# pfetreg.net
KiCad netlist of a schematic drawn in EAGLE
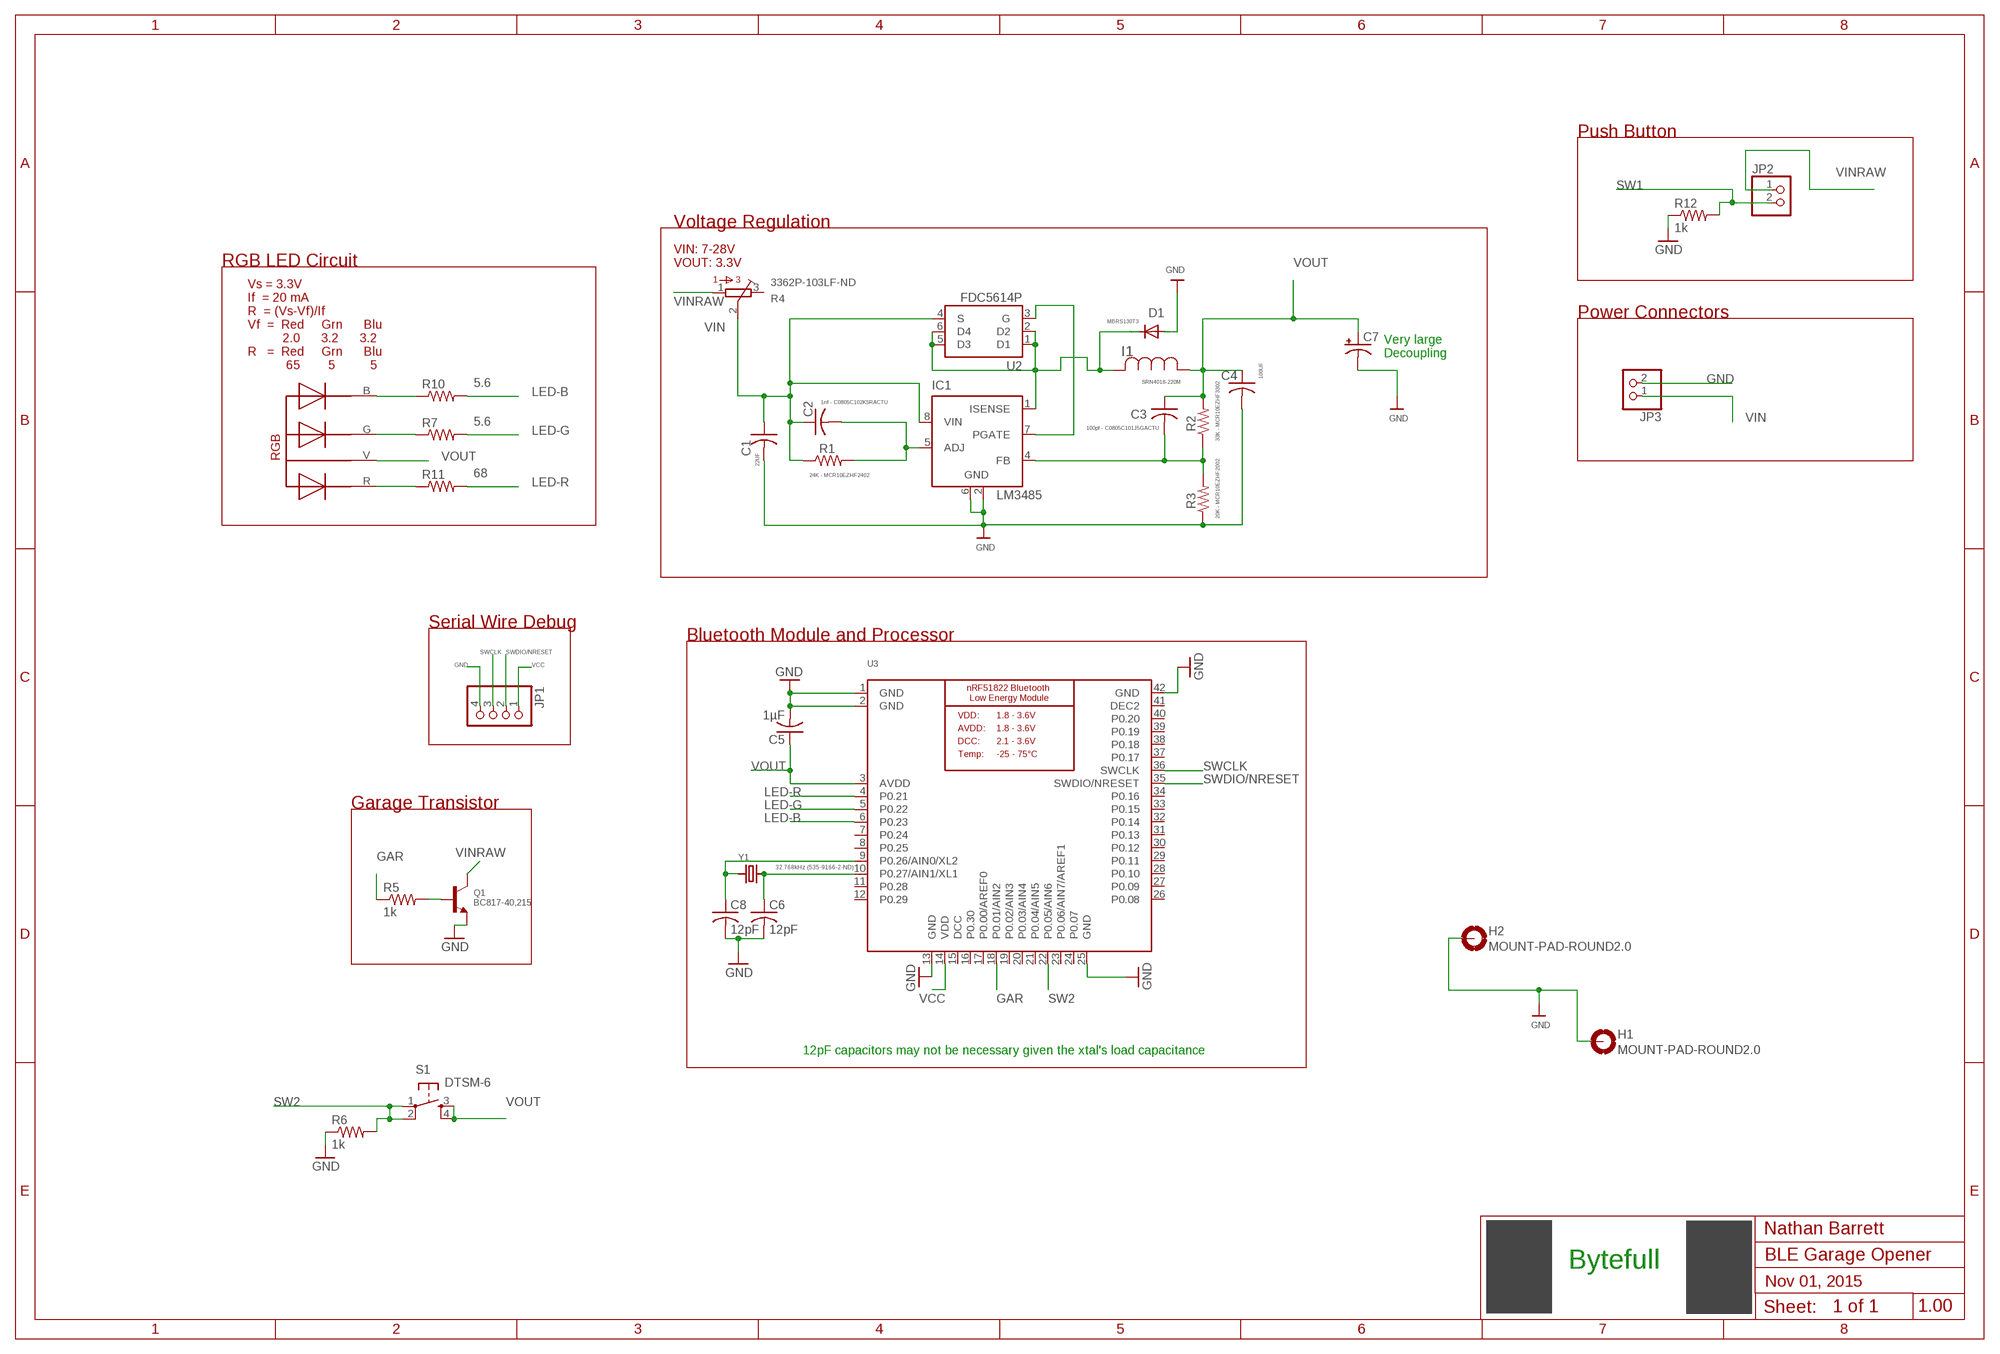
[diagram p0: schematic, sheet 1]

(export (version "E")
  (design (tool "Eeschema 10.0.6"))
  (components
    (comp (ref "C1")
      (value "22UF")
      (footprint "eagle-import:CAPCP7343X430N")
      (fields (field (name "MPN") "F931V226MNC"))
      (libsource (lib "eagle-import") (part "F931V226MNC"))
    )
    (comp (ref "C2")
      (value "1nf - C0805C102K5RACTU")
      (footprint "eagle-import:C0805K")
      (libsource (lib "eagle-import") (part "C-USC0805K"))
    )
    (comp (ref "C3")
      (value "100pf - C0805C101J5GACTU")
      (footprint "eagle-import:C0805K")
      (libsource (lib "eagle-import") (part "C-USC0805K"))
    )
    (comp (ref "C4")
      (value "100UF")
      (footprint "eagle-import:CAPCP7343X430N")
      (fields (field (name "MPN") "6TPC100M"))
      (libsource (lib "eagle-import") (part "6TPC100M"))
    )
    (comp (ref "C5")
      (value "1µF")
      (footprint "eagle-import:C0805K")
      (libsource (lib "eagle-import") (part "HelloWorld_C-USC0805K"))
    )
    (comp (ref "C6")
      (value "12pF")
      (footprint "eagle-import:C0805")
      (libsource (lib "eagle-import") (part "HelloWorld_C-USC0805"))
    )
    (comp (ref "C7")
      (value "CPOL-USE5-10.5")
      (footprint "eagle-import:E5-10,5")
      (libsource (lib "eagle-import") (part "CPOL-USE5-10.5"))
    )
    (comp (ref "C8")
      (value "12pF")
      (footprint "eagle-import:C0805")
      (libsource (lib "eagle-import") (part "HelloWorld_C-USC0805"))
    )
    (comp (ref "D1")
      (value "MBRS130T3")
      (footprint "eagle-import:DO214AA")
      (libsource (lib "eagle-import") (part "DIODE-DO214AA"))
    )
    (comp (ref "H1")
      (value "MOUNT-PAD-ROUND2.0")
      (footprint "eagle-import:2,0-PAD")
      (libsource (lib "eagle-import") (part "MOUNT-PAD-ROUND2.0"))
    )
    (comp (ref "H2")
      (value "MOUNT-PAD-ROUND2.0")
      (footprint "eagle-import:2,0-PAD")
      (libsource (lib "eagle-import") (part "MOUNT-PAD-ROUND2.0"))
    )
    (comp (ref "I1")
      (value "SRN4018-220M")
      (footprint "eagle-import:SRN4018-220M")
      (libsource (lib "eagle-import") (part "SRN4018-220M"))
    )
    (comp (ref "IC1")
      (value "LM3485")
      (footprint "eagle-import:MSOP08")
      (libsource (lib "eagle-import") (part "LM3485"))
    )
    (comp (ref "JP1")
      (value "PINHD-1X4")
      (footprint "eagle-import:1X04")
      (libsource (lib "eagle-import") (part "PINHD-1X4"))
    )
    (comp (ref "JP2")
      (value "PINHD-1X2")
      (footprint "eagle-import:1X02")
      (libsource (lib "eagle-import") (part "PINHD-1X2"))
    )
    (comp (ref "JP3")
      (value "PINHD-1X2")
      (footprint "eagle-import:1X02")
      (libsource (lib "eagle-import") (part "PINHD-1X2"))
    )
    (comp (ref "Q1")
      (value "BC817-40,215")
      (footprint "eagle-import:SOT23-R")
      (libsource (lib "eagle-import") (part "TRANSISTOR_NPN"))
    )
    (comp (ref "R1")
      (value "24K - MCR10EZHF2402")
      (footprint "eagle-import:R0805W")
      (libsource (lib "eagle-import") (part "R-US_R0805W"))
    )
    (comp (ref "R2")
      (value "33K - MCR10EZHF3302")
      (footprint "eagle-import:R0805W")
      (libsource (lib "eagle-import") (part "R-US_R0805W"))
    )
    (comp (ref "R3")
      (value "20K - MCR10EZHF2002")
      (footprint "eagle-import:R0805W")
      (libsource (lib "eagle-import") (part "R-US_R0805W"))
    )
    (comp (ref "R4")
      (value "3362P-103LF-ND")
      (footprint "eagle-import:3362P")
      (libsource (lib "eagle-import") (part "3362P"))
    )
    (comp (ref "R5")
      (value "1k")
      (footprint "eagle-import:R0805")
      (libsource (lib "eagle-import") (part "HelloWorld_R-US_R0805"))
    )
    (comp (ref "R6")
      (value "1k")
      (footprint "eagle-import:R0805")
      (libsource (lib "eagle-import") (part "HelloWorld_R-US_R0805"))
    )
    (comp (ref "R7")
      (value "5.6")
      (footprint "eagle-import:R0805")
      (libsource (lib "eagle-import") (part "HelloWorld_R-US_R0805"))
    )
    (comp (ref "R10")
      (value "5.6")
      (footprint "eagle-import:R0805")
      (libsource (lib "eagle-import") (part "HelloWorld_R-US_R0805"))
    )
    (comp (ref "R11")
      (value "68")
      (footprint "eagle-import:R0805")
      (libsource (lib "eagle-import") (part "HelloWorld_R-US_R0805"))
    )
    (comp (ref "R12")
      (value "1k")
      (footprint "eagle-import:R0805")
      (libsource (lib "eagle-import") (part "HelloWorld_R-US_R0805"))
    )
    (comp (ref "RGB")
      (value "5MMRGBLED")
      (footprint "eagle-import:LED5MMRGB")
      (libsource (lib "eagle-import") (part "5MMRGBLED"))
    )
    (comp (ref "S1")
      (value "DTSM-6")
      (footprint "eagle-import:DTSM-6")
      (libsource (lib "eagle-import") (part "DTSM-6"))
    )
    (comp (ref "U2")
      (value "FDC5614PSOT-23")
      (footprint "eagle-import:SOT23-6")
      (libsource (lib "eagle-import") (part "FDC5614PSOT-23"))
    )
    (comp (ref "U3")
      (value "NRF51822_MODULE_MDBT40")
      (footprint "eagle-import:BLE_MODULE_RAYTAC_MDBT40")
      (libsource (lib "eagle-import") (part "NRF51822_MODULE_MDBT40"))
    )
    (comp (ref "Y1")
      (value "CRYSTAL8X3.8SMT")
      (footprint "eagle-import:CRYSTAL_8X3.8")
      (libsource (lib "eagle-import") (part "CRYSTAL8X3.8SMT"))
    )
  )
  (nets
    (net (code "1") (name "/DCC") (class "Default")
      (node (ref "U3") (pin "15") (pinfunction "DCC_15") (pintype "power_in"))
    )
    (net (code "2") (name "/DEC2") (class "Default")
      (node (ref "U3") (pin "41") (pinfunction "DEC2_41") (pintype "power_in"))
    )
    (net (code "3") (name "/GAR") (class "Default")
      (node (ref "R5") (pin "1") (pinfunction "1_1") (pintype "passive"))
      (node (ref "U3") (pin "18") (pinfunction "P0.01/AIN2_18") (pintype "bidirectional"))
    )
    (net (code "4") (name "/LED-B") (class "Default")
      (node (ref "R10") (pin "2") (pinfunction "2_2") (pintype "passive"))
      (node (ref "U3") (pin "6") (pinfunction "P0.23_6") (pintype "bidirectional"))
    )
    (net (code "5") (name "/LED-G") (class "Default")
      (node (ref "R7") (pin "2") (pinfunction "2_2") (pintype "passive"))
      (node (ref "U3") (pin "5") (pinfunction "P0.22_5") (pintype "bidirectional"))
    )
    (net (code "6") (name "/LED-R") (class "Default")
      (node (ref "R11") (pin "2") (pinfunction "2_2") (pintype "passive"))
      (node (ref "U3") (pin "4") (pinfunction "P0.21_4") (pintype "bidirectional"))
    )
    (net (code "7") (name "/SW1") (class "Default")
      (node (ref "JP2") (pin "2") (pinfunction "2_2") (pintype "passive"))
      (node (ref "R12") (pin "2") (pinfunction "2_2") (pintype "passive"))
    )
    (net (code "8") (name "/SW2") (class "Default")
      (node (ref "R6") (pin "2") (pinfunction "2_2") (pintype "passive"))
      (node (ref "S1") (pin "1") (pinfunction "1_1") (pintype "passive"))
      (node (ref "S1") (pin "2") (pinfunction "2_2") (pintype "passive"))
      (node (ref "U3") (pin "22") (pinfunction "P0.05/AIN6_22") (pintype "bidirectional"))
    )
    (net (code "9") (name "/SWCLK") (class "Default")
      (node (ref "JP1") (pin "3") (pinfunction "3_3") (pintype "passive"))
      (node (ref "U3") (pin "36") (pinfunction "SWCLK_36") (pintype "bidirectional"))
    )
    (net (code "10") (name "/SWDIO{slash}NRESET") (class "Default")
      (node (ref "JP1") (pin "2") (pinfunction "2_2") (pintype "passive"))
      (node (ref "U3") (pin "35") (pinfunction "SWDIO/NRESET_35") (pintype "bidirectional"))
    )
    (net (code "11") (name "/VCC") (class "Default")
      (node (ref "JP1") (pin "1") (pinfunction "1_1") (pintype "passive"))
      (node (ref "U3") (pin "14") (pinfunction "VDD_14") (pintype "power_in"))
    )
    (net (code "12") (name "/VIN") (class "Default")
      (node (ref "C1") (pin "1") (pinfunction "I1_1") (pintype "passive"))
      (node (ref "C2") (pin "1") (pinfunction "1_1") (pintype "passive"))
      (node (ref "IC1") (pin "8") (pinfunction "VIN_8") (pintype "input"))
      (node (ref "JP3") (pin "1") (pinfunction "1_1") (pintype "passive"))
      (node (ref "R1") (pin "1") (pinfunction "1_1") (pintype "passive"))
      (node (ref "R4") (pin "2") (pinfunction "2_2") (pintype "passive"))
      (node (ref "U2") (pin "4") (pinfunction "S_4") (pintype "bidirectional"))
    )
    (net (code "13") (name "/VINRAW") (class "Default")
      (node (ref "JP2") (pin "1") (pinfunction "1_1") (pintype "passive"))
      (node (ref "Q1") (pin "3") (pinfunction "C_3") (pintype "passive"))
      (node (ref "R4") (pin "1") (pinfunction "1_1") (pintype "passive"))
    )
    (net (code "14") (name "/VOUT") (class "Default")
      (node (ref "C3") (pin "1") (pinfunction "1_1") (pintype "passive"))
      (node (ref "C4") (pin "1") (pinfunction "I1_1") (pintype "passive"))
      (node (ref "C5") (pin "1") (pinfunction "1_1") (pintype "passive"))
      (node (ref "C7") (pin "+") (pinfunction "+_+") (pintype "passive"))
      (node (ref "I1") (pin "2") (pinfunction "I2_2") (pintype "passive"))
      (node (ref "R2") (pin "2") (pinfunction "2_2") (pintype "passive"))
      (node (ref "RGB") (pin "V") (pinfunction "V_V") (pintype "bidirectional"))
      (node (ref "S1") (pin "3") (pinfunction "3_3") (pintype "passive"))
      (node (ref "S1") (pin "4") (pinfunction "4_4") (pintype "passive"))
      (node (ref "U3") (pin "3") (pinfunction "AVDD_3") (pintype "power_in"))
    )
    (net (code "15") (name "GND") (class "Default")
      (node (ref "C1") (pin "2") (pinfunction "I2_2") (pintype "passive"))
      (node (ref "C4") (pin "2") (pinfunction "I2_2") (pintype "passive"))
      (node (ref "C5") (pin "2") (pinfunction "2_2") (pintype "passive"))
      (node (ref "C6") (pin "2") (pinfunction "2_2") (pintype "passive"))
      (node (ref "C7") (pin "-") (pinfunction "-_-") (pintype "passive"))
      (node (ref "C8") (pin "2") (pinfunction "2_2") (pintype "passive"))
      (node (ref "D1") (pin "A") (pinfunction "A_A") (pintype "passive"))
      (node (ref "H1") (pin "B2,8") (pinfunction "MOUNT_B2,8") (pintype "passive"))
      (node (ref "H2") (pin "B2,8") (pinfunction "MOUNT_B2,8") (pintype "passive"))
      (node (ref "IC1") (pin "2") (pinfunction "GND_2") (pintype "power_in"))
      (node (ref "IC1") (pin "6") (pinfunction "GND_6") (pintype "power_in"))
      (node (ref "JP1") (pin "4") (pinfunction "4_4") (pintype "passive"))
      (node (ref "JP3") (pin "2") (pinfunction "2_2") (pintype "passive"))
      (node (ref "Q1") (pin "2") (pinfunction "E_2") (pintype "passive"))
      (node (ref "R12") (pin "1") (pinfunction "1_1") (pintype "passive"))
      (node (ref "R3") (pin "1") (pinfunction "1_1") (pintype "passive"))
      (node (ref "R6") (pin "1") (pinfunction "1_1") (pintype "passive"))
      (node (ref "U3") (pin "1") (pinfunction "GND_1") (pintype "power_in"))
      (node (ref "U3") (pin "13") (pinfunction "GND_13") (pintype "power_in"))
      (node (ref "U3") (pin "2") (pinfunction "GND_2") (pintype "power_in"))
      (node (ref "U3") (pin "25") (pinfunction "GND_25") (pintype "power_in"))
      (node (ref "U3") (pin "42") (pinfunction "GND_42") (pintype "power_in"))
    )
    (net (code "16") (name "Net-(I1-I1)") (class "Default")
      (node (ref "D1") (pin "C") (pinfunction "C_C") (pintype "passive"))
      (node (ref "I1") (pin "1") (pinfunction "I1_1") (pintype "passive"))
      (node (ref "IC1") (pin "1") (pinfunction "ISENSE_1") (pintype "input"))
      (node (ref "U2") (pin "1") (pinfunction "D1_1") (pintype "bidirectional"))
      (node (ref "U2") (pin "2") (pinfunction "D2_2") (pintype "bidirectional"))
      (node (ref "U2") (pin "5") (pinfunction "D3_5") (pintype "bidirectional"))
      (node (ref "U2") (pin "6") (pinfunction "D4_6") (pintype "bidirectional"))
    )
    (net (code "17") (name "Net-(IC1-ADJ)") (class "Default")
      (node (ref "C2") (pin "2") (pinfunction "2_2") (pintype "passive"))
      (node (ref "IC1") (pin "5") (pinfunction "ADJ_5") (pintype "input"))
      (node (ref "R1") (pin "2") (pinfunction "2_2") (pintype "passive"))
    )
    (net (code "18") (name "Net-(IC1-FB)") (class "Default")
      (node (ref "C3") (pin "2") (pinfunction "2_2") (pintype "passive"))
      (node (ref "IC1") (pin "4") (pinfunction "FB_4") (pintype "input"))
      (node (ref "R2") (pin "1") (pinfunction "1_1") (pintype "passive"))
      (node (ref "R3") (pin "2") (pinfunction "2_2") (pintype "passive"))
    )
    (net (code "19") (name "Net-(IC1-PGATE)") (class "Default")
      (node (ref "IC1") (pin "7") (pinfunction "PGATE_7") (pintype "output"))
      (node (ref "U2") (pin "3") (pinfunction "G_3") (pintype "bidirectional"))
    )
    (net (code "20") (name "Net-(Q1-B)") (class "Default")
      (node (ref "Q1") (pin "1") (pinfunction "B_1") (pintype "passive"))
      (node (ref "R5") (pin "2") (pinfunction "2_2") (pintype "passive"))
    )
    (net (code "21") (name "Net-(R7-Pad1)") (class "Default")
      (node (ref "R7") (pin "1") (pinfunction "1_1") (pintype "passive"))
      (node (ref "RGB") (pin "G") (pinfunction "G_G") (pintype "bidirectional"))
    )
    (net (code "22") (name "Net-(R10-Pad1)") (class "Default")
      (node (ref "R10") (pin "1") (pinfunction "1_1") (pintype "passive"))
      (node (ref "RGB") (pin "B") (pinfunction "B_B") (pintype "bidirectional"))
    )
    (net (code "23") (name "Net-(R11-Pad1)") (class "Default")
      (node (ref "R11") (pin "1") (pinfunction "1_1") (pintype "passive"))
      (node (ref "RGB") (pin "R") (pinfunction "R_R") (pintype "bidirectional"))
    )
    (net (code "24") (name "Net-(U3-P0.26{slash}AIN0{slash}XL2)") (class "Default")
      (node (ref "C8") (pin "1") (pinfunction "1_1") (pintype "passive"))
      (node (ref "U3") (pin "9") (pinfunction "P0.26/AIN0/XL2_9") (pintype "bidirectional"))
      (node (ref "Y1") (pin "P$1") (pinfunction "1_P$1") (pintype "passive"))
    )
    (net (code "25") (name "Net-(U3-P0.27{slash}AIN1{slash}XL1)") (class "Default")
      (node (ref "C6") (pin "1") (pinfunction "1_1") (pintype "passive"))
      (node (ref "U3") (pin "10") (pinfunction "P0.27/AIN1/XL1_10") (pintype "bidirectional"))
      (node (ref "Y1") (pin "P$4") (pinfunction "2_P$4") (pintype "passive"))
    )
    (net (code "26") (name "unconnected-(R4-Pad3)") (class "Default")
      (node (ref "R4") (pin "3") (pinfunction "3_3") (pintype "passive"))
    )
    (net (code "27") (name "unconnected-(U3-P0.00{slash}AREF0-Pad17)") (class "Default")
      (node (ref "U3") (pin "17") (pinfunction "P0.00/AREF0_17") (pintype "bidirectional"))
    )
    (net (code "28") (name "unconnected-(U3-P0.02{slash}AIN3-Pad19)") (class "Default")
      (node (ref "U3") (pin "19") (pinfunction "P0.02/AIN3_19") (pintype "bidirectional"))
    )
    (net (code "29") (name "unconnected-(U3-P0.03{slash}AIN4-Pad20)") (class "Default")
      (node (ref "U3") (pin "20") (pinfunction "P0.03/AIN4_20") (pintype "bidirectional"))
    )
    (net (code "30") (name "unconnected-(U3-P0.04{slash}AIN5-Pad21)") (class "Default")
      (node (ref "U3") (pin "21") (pinfunction "P0.04/AIN5_21") (pintype "bidirectional"))
    )
    (net (code "31") (name "unconnected-(U3-P0.06{slash}AIN7{slash}AREF1-Pad23)") (class "Default")
      (node (ref "U3") (pin "23") (pinfunction "P0.06/AIN7/AREF1_23") (pintype "bidirectional"))
    )
    (net (code "32") (name "unconnected-(U3-P0.07-Pad24)") (class "Default")
      (node (ref "U3") (pin "24") (pinfunction "P0.07_24") (pintype "bidirectional"))
    )
    (net (code "33") (name "unconnected-(U3-P0.08-Pad26)") (class "Default")
      (node (ref "U3") (pin "26") (pinfunction "P0.08_26") (pintype "bidirectional"))
    )
    (net (code "34") (name "unconnected-(U3-P0.09-Pad27)") (class "Default")
      (node (ref "U3") (pin "27") (pinfunction "P0.09_27") (pintype "bidirectional"))
    )
    (net (code "35") (name "unconnected-(U3-P0.10-Pad28)") (class "Default")
      (node (ref "U3") (pin "28") (pinfunction "P0.10_28") (pintype "bidirectional"))
    )
    (net (code "36") (name "unconnected-(U3-P0.11-Pad29)") (class "Default")
      (node (ref "U3") (pin "29") (pinfunction "P0.11_29") (pintype "bidirectional"))
    )
    (net (code "37") (name "unconnected-(U3-P0.12-Pad30)") (class "Default")
      (node (ref "U3") (pin "30") (pinfunction "P0.12_30") (pintype "bidirectional"))
    )
    (net (code "38") (name "unconnected-(U3-P0.13-Pad31)") (class "Default")
      (node (ref "U3") (pin "31") (pinfunction "P0.13_31") (pintype "bidirectional"))
    )
    (net (code "39") (name "unconnected-(U3-P0.14-Pad32)") (class "Default")
      (node (ref "U3") (pin "32") (pinfunction "P0.14_32") (pintype "bidirectional"))
    )
    (net (code "40") (name "unconnected-(U3-P0.15-Pad33)") (class "Default")
      (node (ref "U3") (pin "33") (pinfunction "P0.15_33") (pintype "bidirectional"))
    )
    (net (code "41") (name "unconnected-(U3-P0.16-Pad34)") (class "Default")
      (node (ref "U3") (pin "34") (pinfunction "P0.16_34") (pintype "bidirectional"))
    )
    (net (code "42") (name "unconnected-(U3-P0.17-Pad37)") (class "Default")
      (node (ref "U3") (pin "37") (pinfunction "P0.17_37") (pintype "bidirectional"))
    )
    (net (code "43") (name "unconnected-(U3-P0.18-Pad38)") (class "Default")
      (node (ref "U3") (pin "38") (pinfunction "P0.18_38") (pintype "bidirectional"))
    )
    (net (code "44") (name "unconnected-(U3-P0.19-Pad39)") (class "Default")
      (node (ref "U3") (pin "39") (pinfunction "P0.19_39") (pintype "bidirectional"))
    )
    (net (code "45") (name "unconnected-(U3-P0.20-Pad40)") (class "Default")
      (node (ref "U3") (pin "40") (pinfunction "P0.20_40") (pintype "bidirectional"))
    )
    (net (code "46") (name "unconnected-(U3-P0.24-Pad7)") (class "Default")
      (node (ref "U3") (pin "7") (pinfunction "P0.24_7") (pintype "bidirectional"))
    )
    (net (code "47") (name "unconnected-(U3-P0.25-Pad8)") (class "Default")
      (node (ref "U3") (pin "8") (pinfunction "P0.25_8") (pintype "bidirectional"))
    )
    (net (code "48") (name "unconnected-(U3-P0.28-Pad11)") (class "Default")
      (node (ref "U3") (pin "11") (pinfunction "P0.28_11") (pintype "bidirectional"))
    )
    (net (code "49") (name "unconnected-(U3-P0.29-Pad12)") (class "Default")
      (node (ref "U3") (pin "12") (pinfunction "P0.29_12") (pintype "bidirectional"))
    )
    (net (code "50") (name "unconnected-(U3-P0.30-Pad16)") (class "Default")
      (node (ref "U3") (pin "16") (pinfunction "P0.30_16") (pintype "bidirectional"))
    )
  )
)
